# Power.net
KiCad netlist of a schematic drawn in Altium Designer
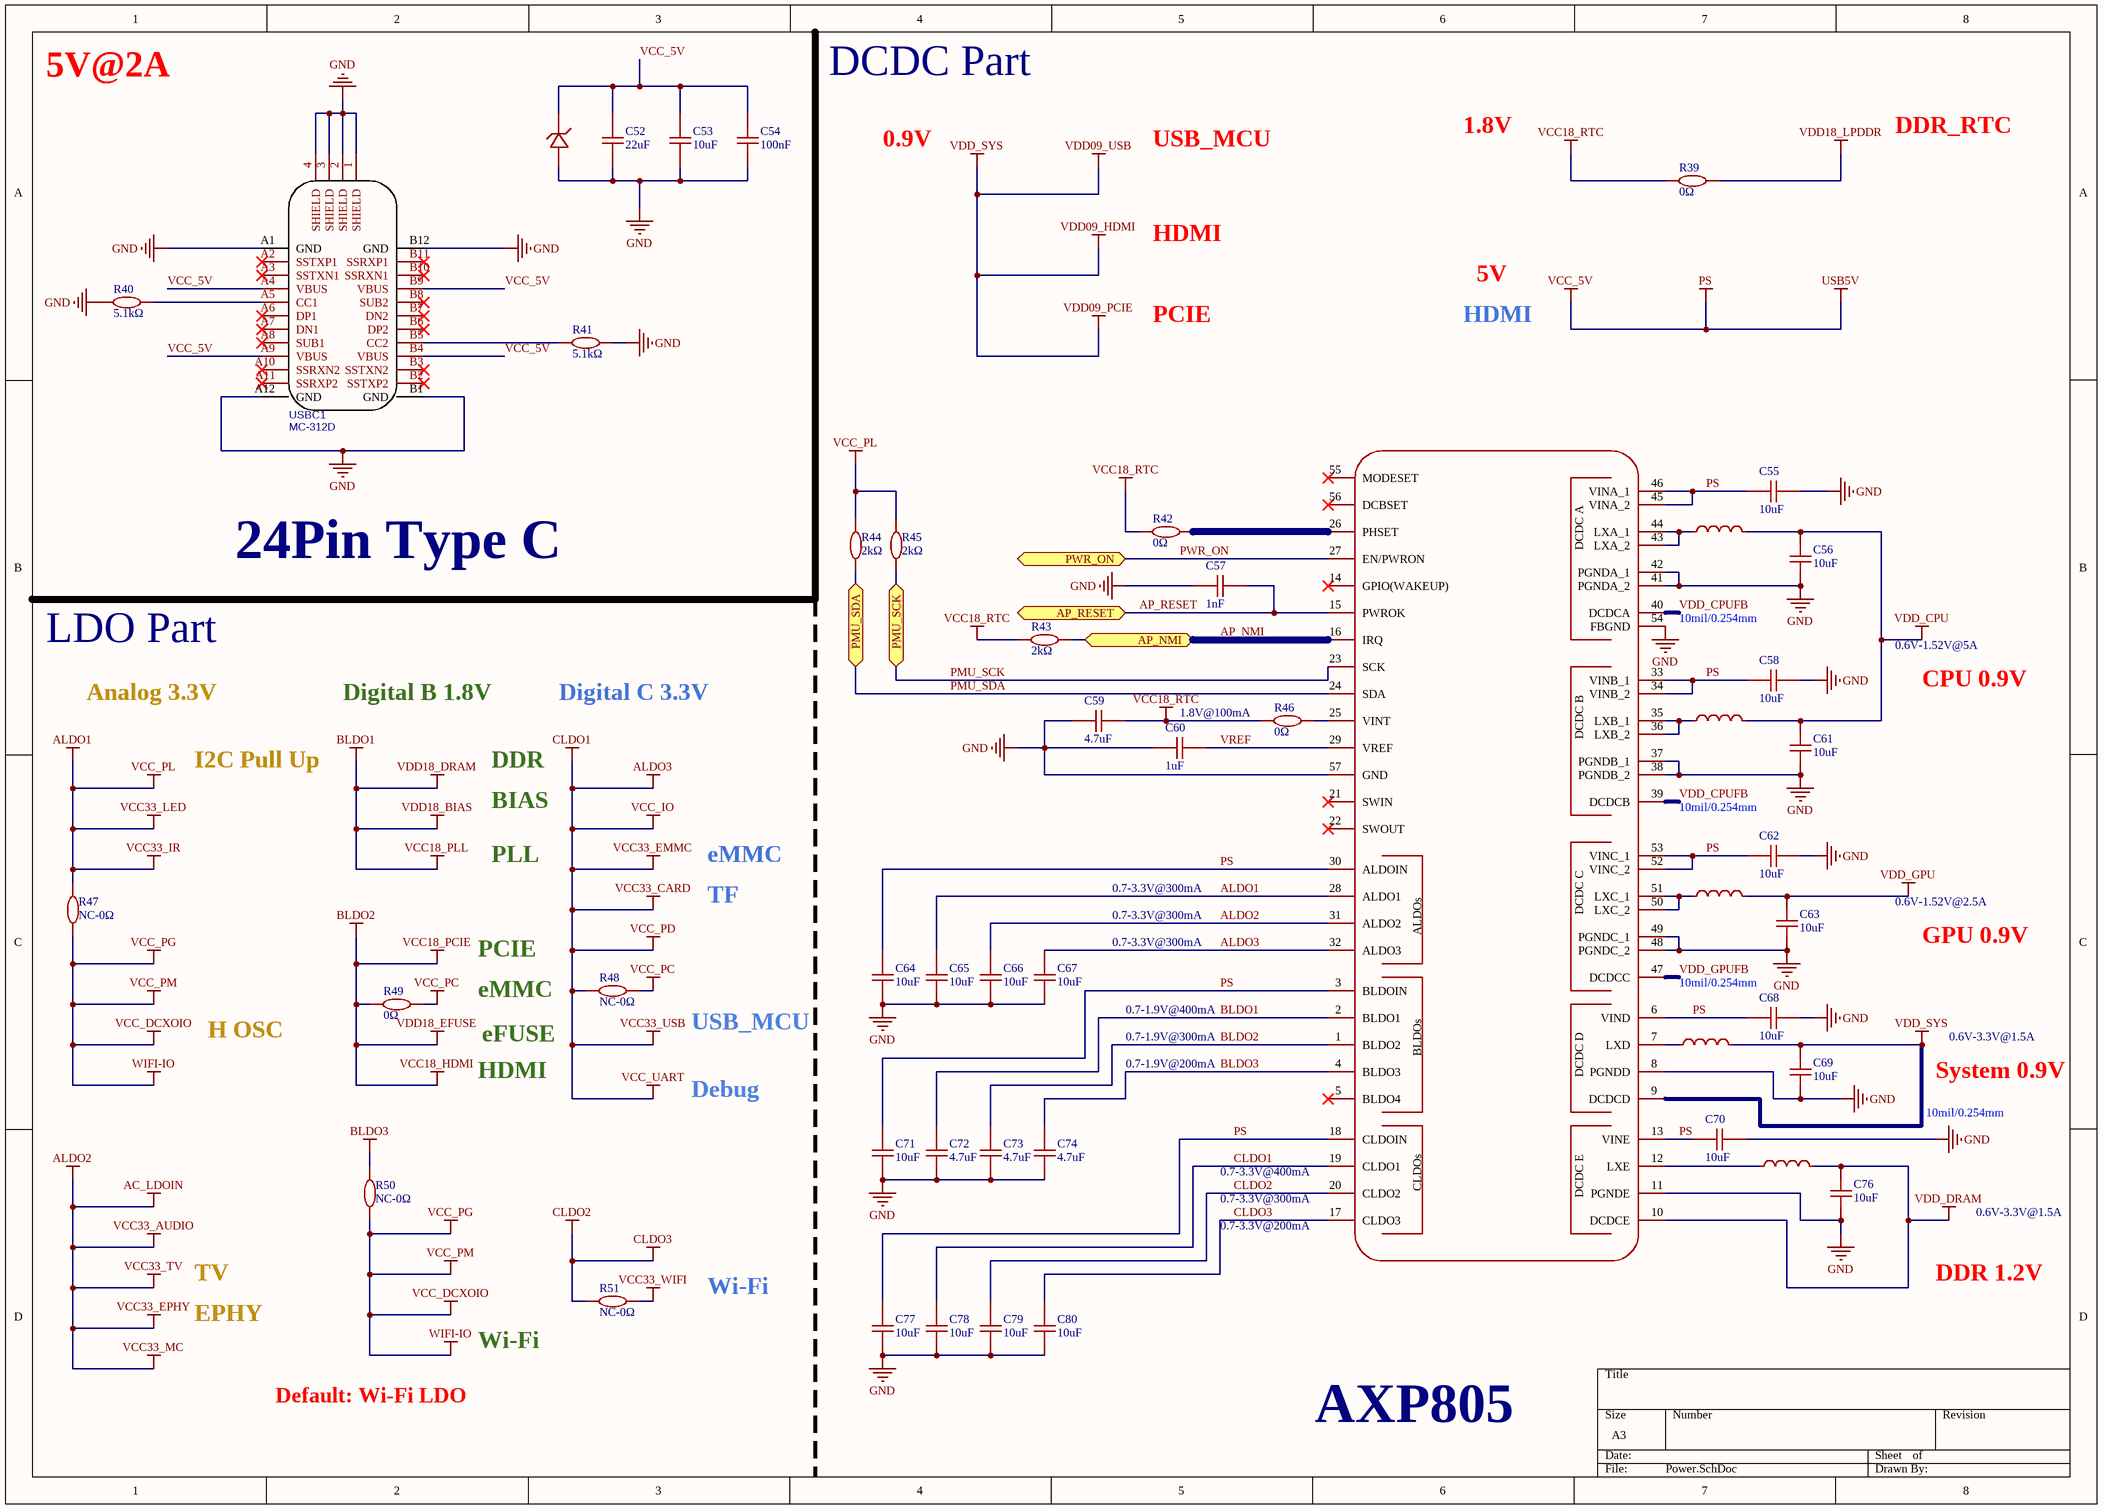
[diagram p0: Power.SchDoc]

(export (version "E")
  (design (tool "Eeschema 10.0.6"))
  (components
    (comp (ref "C52")
      (value "22uF")
      (footprint "C0603")
      (description "16V 22uF X5R ±20% 0603 Ceramic Capacitors ROHS")
      (libsource (lib "RLC") (part "22uF"))
    )
    (comp (ref "C53")
      (value "10uF")
      (footprint "C0603")
      (description "10V 10uF X5R ±10% 0603 Ceramic Capacitors ROHS")
      (libsource (lib "RLC") (part "10uF"))
    )
    (comp (ref "C54")
      (value "100nF")
      (footprint "C0402")
      (description "50V 100nF X7R ±10% 0402 Ceramic Capacitors ROHS")
      (libsource (lib "RLC") (part "100nF"))
    )
    (comp (ref "C55")
      (value "10uF")
      (footprint "C0603")
      (description "10V 10uF X5R ±10% 0603 Ceramic Capacitors ROHS")
      (libsource (lib "RLC") (part "10uF"))
    )
    (comp (ref "C56")
      (value "10uF")
      (footprint "C0603")
      (description "10V 10uF X5R ±10% 0603 Ceramic Capacitors ROHS")
      (libsource (lib "RLC") (part "10uF"))
    )
    (comp (ref "C57")
      (value "1nF")
      (footprint "C0402")
      (description "50V 1nF X7R ±10% 0402 Ceramic Capacitors ROHS")
      (libsource (lib "RLC") (part "1nF"))
    )
    (comp (ref "C58")
      (value "10uF")
      (footprint "C0603")
      (description "10V 10uF X5R ±10% 0603 Ceramic Capacitors ROHS")
      (libsource (lib "RLC") (part "10uF"))
    )
    (comp (ref "C59")
      (value "4.7uF")
      (footprint "C0402")
      (description "10V 4.7uF X5R ±20% 0402 Ceramic Capacitors ROHS")
      (libsource (lib "RLC") (part "4.7uF"))
    )
    (comp (ref "C60")
      (value "1uF")
      (footprint "C0402")
      (description "50V 1uF X5R ±10% 0402 Ceramic Capacitors ROHS")
      (libsource (lib "RLC") (part "1uF"))
    )
    (comp (ref "C61")
      (value "10uF")
      (footprint "C0603")
      (description "10V 10uF X5R ±10% 0603 Ceramic Capacitors ROHS")
      (libsource (lib "RLC") (part "10uF"))
    )
    (comp (ref "C62")
      (value "10uF")
      (footprint "C0603")
      (description "10V 10uF X5R ±10% 0603 Ceramic Capacitors ROHS")
      (libsource (lib "RLC") (part "10uF"))
    )
    (comp (ref "C63")
      (value "10uF")
      (footprint "C0603")
      (description "10V 10uF X5R ±10% 0603 Ceramic Capacitors ROHS")
      (libsource (lib "RLC") (part "10uF"))
    )
    (comp (ref "C64")
      (value "10uF")
      (footprint "C0603")
      (description "10V 10uF X5R ±10% 0603 Ceramic Capacitors ROHS")
      (libsource (lib "RLC") (part "10uF"))
    )
    (comp (ref "C65")
      (value "10uF")
      (footprint "C0603")
      (description "10V 10uF X5R ±10% 0603 Ceramic Capacitors ROHS")
      (libsource (lib "RLC") (part "10uF"))
    )
    (comp (ref "C66")
      (value "10uF")
      (footprint "C0603")
      (description "10V 10uF X5R ±10% 0603 Ceramic Capacitors ROHS")
      (libsource (lib "RLC") (part "10uF"))
    )
    (comp (ref "C67")
      (value "10uF")
      (footprint "C0603")
      (description "10V 10uF X5R ±10% 0603 Ceramic Capacitors ROHS")
      (libsource (lib "RLC") (part "10uF"))
    )
    (comp (ref "C68")
      (value "10uF")
      (footprint "C0603")
      (description "10V 10uF X5R ±10% 0603 Ceramic Capacitors ROHS")
      (libsource (lib "RLC") (part "10uF"))
    )
    (comp (ref "C69")
      (value "10uF")
      (footprint "C0603")
      (description "10V 10uF X5R ±10% 0603 Ceramic Capacitors ROHS")
      (libsource (lib "RLC") (part "10uF"))
    )
    (comp (ref "C70")
      (value "10uF")
      (footprint "C0603")
      (description "10V 10uF X5R ±10% 0603 Ceramic Capacitors ROHS")
      (libsource (lib "RLC") (part "10uF"))
    )
    (comp (ref "C71")
      (value "10uF")
      (footprint "C0603")
      (description "10V 10uF X5R ±10% 0603 Ceramic Capacitors ROHS")
      (libsource (lib "RLC") (part "10uF"))
    )
    (comp (ref "C72")
      (value "4.7uF")
      (footprint "C0402")
      (description "10V 4.7uF X5R ±20% 0402 Ceramic Capacitors ROHS")
      (libsource (lib "RLC") (part "4.7uF"))
    )
    (comp (ref "C73")
      (value "4.7uF")
      (footprint "C0402")
      (description "10V 4.7uF X5R ±20% 0402 Ceramic Capacitors ROHS")
      (libsource (lib "RLC") (part "4.7uF"))
    )
    (comp (ref "C74")
      (value "4.7uF")
      (footprint "C0402")
      (description "10V 4.7uF X5R ±20% 0402 Ceramic Capacitors ROHS")
      (libsource (lib "RLC") (part "4.7uF"))
    )
    (comp (ref "C76")
      (value "10uF")
      (footprint "C0603")
      (description "10V 10uF X5R ±10% 0603 Ceramic Capacitors ROHS")
      (libsource (lib "RLC") (part "10uF"))
    )
    (comp (ref "C77")
      (value "10uF")
      (footprint "C0603")
      (description "10V 10uF X5R ±10% 0603 Ceramic Capacitors ROHS")
      (libsource (lib "RLC") (part "10uF"))
    )
    (comp (ref "C78")
      (value "10uF")
      (footprint "C0603")
      (description "10V 10uF X5R ±10% 0603 Ceramic Capacitors ROHS")
      (libsource (lib "RLC") (part "10uF"))
    )
    (comp (ref "C79")
      (value "10uF")
      (footprint "C0603")
      (description "10V 10uF X5R ±10% 0603 Ceramic Capacitors ROHS")
      (libsource (lib "RLC") (part "10uF"))
    )
    (comp (ref "C80")
      (value "10uF")
      (footprint "C0603")
      (description "10V 10uF X5R ±10% 0603 Ceramic Capacitors ROHS")
      (libsource (lib "RLC") (part "10uF"))
    )
    (comp (ref "D5")
      (value "SMAJ5.0A")
      (footprint "SMA_L4.3-W2.6-LS5.2-RD")
      (description "43.5A 400W 9.2V 6.4V Unidirectional 5V DO-214AC(SMA) TVS Diodes ROHS")
      (fields (field (name "MANUFACTURER") "Littelfuse(美国力特)"))
      (libsource (lib "LED") (part "SMAJ5.0A_C83329"))
    )
    (comp (ref "L2")
      (value "1.5uH")
      (footprint "IND-SMD_L4.0-W4.0")
      (description "4.15A 1.5uH ±30% 18mΩ SMD,4x4mm Fixed Inductors ROHS")
      (fields
        (field (name "MANUFACTURER") "Sunltech(顺磁)")
        (field (name "MANUFACTURER PART") "SLW4030S1R0NST")
      )
      (libsource (lib "RLC") (part "SLW4030S1R5NST"))
    )
    (comp (ref "L3")
      (value "1.5uH")
      (footprint "IND-SMD_L4.0-W4.0")
      (description "4.15A 1.5uH ±30% 18mΩ SMD,4x4mm Fixed Inductors ROHS")
      (fields
        (field (name "MANUFACTURER") "Sunltech(顺磁)")
        (field (name "MANUFACTURER PART") "SLW4030S1R0NST")
      )
      (libsource (lib "RLC") (part "SLW4030S1R5NST"))
    )
    (comp (ref "L4")
      (value "1.5uH")
      (footprint "IND-SMD_L4.0-W4.0")
      (description "4.15A 1.5uH ±30% 18mΩ SMD,4x4mm Fixed Inductors ROHS")
      (fields
        (field (name "MANUFACTURER") "Sunltech(顺磁)")
        (field (name "MANUFACTURER PART") "SLW4030S1R0NST")
      )
      (libsource (lib "RLC") (part "SLW4030S1R5NST"))
    )
    (comp (ref "L5")
      (value "1.5uH")
      (footprint "IND-SMD_L4.0-W4.0")
      (description "4.15A 1.5uH ±30% 18mΩ SMD,4x4mm Fixed Inductors ROHS")
      (fields
        (field (name "MANUFACTURER") "Sunltech(顺磁)")
        (field (name "MANUFACTURER PART") "SLW4030S1R0NST")
      )
      (libsource (lib "RLC") (part "SLW4030S1R5NST"))
    )
    (comp (ref "L6")
      (value "1.5uH")
      (footprint "IND-SMD_L4.0-W4.0")
      (description "4.15A 1.5uH ±30% 18mΩ SMD,4x4mm Fixed Inductors ROHS")
      (fields
        (field (name "MANUFACTURER") "Sunltech(顺磁)")
        (field (name "MANUFACTURER PART") "SLW4030S1R0NST")
      )
      (libsource (lib "RLC") (part "SLW4030S1R5NST"))
    )
    (comp (ref "R39")
      (value "0Ω")
      (footprint "R0402")
      (description "0Ω 62.5mW 50V Thick Film Resistor ±1% 0402 Chip Resistor - Surface Mount ROHS")
      (libsource (lib "RLC") (part "0Ω"))
    )
    (comp (ref "R40")
      (value "5.1kΩ")
      (footprint "R0402")
      (description "5.1kΩ 62.5mW 50V ±100ppm/℃ Thick Film Resistor ±1% 0402 Chip Resistor - Surface Mount ROHS")
      (libsource (lib "RLC") (part "5.1kΩ"))
    )
    (comp (ref "R41")
      (value "5.1kΩ")
      (footprint "R0402")
      (description "5.1kΩ 62.5mW 50V ±100ppm/℃ Thick Film Resistor ±1% 0402 Chip Resistor - Surface Mount ROHS")
      (libsource (lib "RLC") (part "5.1kΩ"))
    )
    (comp (ref "R42")
      (value "0Ω")
      (footprint "R0402")
      (description "0Ω 62.5mW 50V Thick Film Resistor ±1% 0402 Chip Resistor - Surface Mount ROHS")
      (libsource (lib "RLC") (part "0Ω"))
    )
    (comp (ref "R43")
      (value "2kΩ")
      (footprint "R0402")
      (description "100mW 2kΩ 75V ±100ppm/℃ Thick Film Resistor ±1% 0402 Chip Resistor - Surface Mount ROHS")
      (libsource (lib "RLC") (part "2kΩ"))
    )
    (comp (ref "R44")
      (value "2kΩ")
      (footprint "R0402")
      (description "100mW 2kΩ 75V ±100ppm/℃ Thick Film Resistor ±1% 0402 Chip Resistor - Surface Mount ROHS")
      (libsource (lib "RLC") (part "2kΩ"))
    )
    (comp (ref "R45")
      (value "2kΩ")
      (footprint "R0402")
      (description "100mW 2kΩ 75V ±100ppm/℃ Thick Film Resistor ±1% 0402 Chip Resistor - Surface Mount ROHS")
      (libsource (lib "RLC") (part "2kΩ"))
    )
    (comp (ref "R46")
      (value "0Ω")
      (footprint "R0402")
      (description "0Ω 62.5mW 50V Thick Film Resistor ±1% 0402 Chip Resistor - Surface Mount ROHS")
      (libsource (lib "RLC") (part "0Ω"))
    )
    (comp (ref "R47")
      (value "NC-0Ω")
      (footprint "R0402")
      (description "0Ω 62.5mW 50V Thick Film Resistor ±1% 0402 Chip Resistor - Surface Mount ROHS")
      (libsource (lib "RLC") (part "0Ω"))
    )
    (comp (ref "R48")
      (value "NC-0Ω")
      (footprint "R0402")
      (description "0Ω 62.5mW 50V Thick Film Resistor ±1% 0402 Chip Resistor - Surface Mount ROHS")
      (libsource (lib "RLC") (part "0Ω"))
    )
    (comp (ref "R49")
      (value "0Ω")
      (footprint "R0402")
      (description "0Ω 62.5mW 50V Thick Film Resistor ±1% 0402 Chip Resistor - Surface Mount ROHS")
      (libsource (lib "RLC") (part "0Ω"))
    )
    (comp (ref "R50")
      (value "NC-0Ω")
      (footprint "R0402")
      (description "0Ω 62.5mW 50V Thick Film Resistor ±1% 0402 Chip Resistor - Surface Mount ROHS")
      (libsource (lib "RLC") (part "0Ω"))
    )
    (comp (ref "R51")
      (value "NC-0Ω")
      (footprint "R0402")
      (description "0Ω 62.5mW 50V Thick Film Resistor ±1% 0402 Chip Resistor - Surface Mount ROHS")
      (libsource (lib "RLC") (part "0Ω"))
    )
    (comp (ref "U4")
      (value "AXP805")
      (footprint "QFN-56_L7.0-W7.0-P0.40-TL-EP4.6")
      (libsource (lib "IC") (part "AXP805"))
    )
    (comp (ref "USBC1")
      (value "MC-312D")
      (footprint "USB-C-SMD_MC-312D-C")
      (description "1 24P Type-C SMD USB, DVI, HDMI Connector Assemblies ROHS")
      (fields
        (field (name "MANUFACTURER") "SOFNG(硕方)")
        (field (name "MANUFACTURER PART") "MC-312D-C")
        (field (name "CONTRIBUTOR") "LCSC")
      )
      (libsource (lib "Connector") (part "MC-312D"))
    )
  )
  (nets
    (net (code "1") (name "/AP_NMI") (class "Default")
      (node (ref "R43") (pin "2") (pinfunction "2_2") (pintype "passive"))
      (node (ref "U4") (pin "16") (pinfunction "IRQ_16") (pintype "passive"))
    )
    (net (code "2") (name "/AP_RESET") (class "Default")
      (node (ref "C57") (pin "2") (pinfunction "2_2") (pintype "passive"))
      (node (ref "U4") (pin "15") (pinfunction "PWROK_15") (pintype "passive"))
    )
    (net (code "3") (name "/PMU_SCK") (class "Default")
      (node (ref "R45") (pin "1") (pinfunction "1_1") (pintype "passive"))
      (node (ref "U4") (pin "23") (pinfunction "SCK_23") (pintype "passive"))
    )
    (net (code "4") (name "/PMU_SDA") (class "Default")
      (node (ref "R44") (pin "1") (pinfunction "1_1") (pintype "passive"))
      (node (ref "U4") (pin "24") (pinfunction "SDA_24") (pintype "passive"))
    )
    (net (code "5") (name "/PWR_ON") (class "Default")
      (node (ref "U4") (pin "27") (pinfunction "EN/PWRON_27") (pintype "passive"))
    )
    (net (code "6") (name "/VDD_CPUFB") (class "Default")
      (node (ref "U4") (pin "39") (pinfunction "DCDCB_39") (pintype "passive"))
      (node (ref "U4") (pin "40") (pinfunction "DCDCA_40") (pintype "passive"))
    )
    (net (code "7") (name "/VDD_GPUFB") (class "Default")
      (node (ref "U4") (pin "47") (pinfunction "DCDCC_47") (pintype "passive"))
    )
    (net (code "8") (name "/VREF") (class "Default")
      (node (ref "C60") (pin "2") (pinfunction "2_2") (pintype "passive"))
      (node (ref "U4") (pin "29") (pinfunction "VREF_29") (pintype "passive"))
    )
    (net (code "9") (name "AC_LDOIN") (class "Default")
      (node (ref "C66") (pin "2") (pinfunction "2_2") (pintype "passive"))
      (node (ref "U4") (pin "31") (pinfunction "ALDO2_31") (pintype "passive"))
    )
    (net (code "10") (name "ALDO1") (class "Default")
      (node (ref "C65") (pin "2") (pinfunction "2_2") (pintype "passive"))
      (node (ref "R44") (pin "2") (pinfunction "2_2") (pintype "passive"))
      (node (ref "R45") (pin "2") (pinfunction "2_2") (pintype "passive"))
      (node (ref "R47") (pin "2") (pinfunction "2_2") (pintype "passive"))
      (node (ref "U4") (pin "28") (pinfunction "ALDO1_28") (pintype "passive"))
    )
    (net (code "11") (name "ALDO3") (class "Default")
      (node (ref "C67") (pin "2") (pinfunction "2_2") (pintype "passive"))
      (node (ref "C78") (pin "2") (pinfunction "2_2") (pintype "passive"))
      (node (ref "R48") (pin "2") (pinfunction "2_2") (pintype "passive"))
      (node (ref "U4") (pin "19") (pinfunction "CLDO1_19") (pintype "passive"))
      (node (ref "U4") (pin "32") (pinfunction "ALDO3_32") (pintype "passive"))
    )
    (net (code "12") (name "BLDO1") (class "Default")
      (node (ref "C72") (pin "2") (pinfunction "2_2") (pintype "passive"))
      (node (ref "U4") (pin "2") (pinfunction "BLDO1_2") (pintype "passive"))
    )
    (net (code "13") (name "BLDO2") (class "Default")
      (node (ref "C73") (pin "2") (pinfunction "2_2") (pintype "passive"))
      (node (ref "R49") (pin "1") (pinfunction "1_1") (pintype "passive"))
      (node (ref "U4") (pin "1") (pinfunction "BLDO2_1") (pintype "passive"))
    )
    (net (code "14") (name "BLDO3") (class "Default")
      (node (ref "C74") (pin "2") (pinfunction "2_2") (pintype "passive"))
      (node (ref "R50") (pin "2") (pinfunction "2_2") (pintype "passive"))
      (node (ref "U4") (pin "4") (pinfunction "BLDO3_4") (pintype "passive"))
    )
    (net (code "15") (name "CLDO2") (class "Default")
      (node (ref "C79") (pin "2") (pinfunction "2_2") (pintype "passive"))
      (node (ref "C80") (pin "2") (pinfunction "2_2") (pintype "passive"))
      (node (ref "R51") (pin "2") (pinfunction "2_2") (pintype "passive"))
      (node (ref "U4") (pin "17") (pinfunction "CLDO3_17") (pintype "passive"))
      (node (ref "U4") (pin "20") (pinfunction "CLDO2_20") (pintype "passive"))
    )
    (net (code "16") (name "GND") (class "Default")
      (node (ref "C52") (pin "1") (pinfunction "1_1") (pintype "passive"))
      (node (ref "C53") (pin "1") (pinfunction "1_1") (pintype "passive"))
      (node (ref "C54") (pin "1") (pinfunction "1_1") (pintype "passive"))
      (node (ref "C55") (pin "1") (pinfunction "1_1") (pintype "passive"))
      (node (ref "C56") (pin "1") (pinfunction "1_1") (pintype "passive"))
      (node (ref "C57") (pin "1") (pinfunction "1_1") (pintype "passive"))
      (node (ref "C58") (pin "1") (pinfunction "1_1") (pintype "passive"))
      (node (ref "C59") (pin "1") (pinfunction "1_1") (pintype "passive"))
      (node (ref "C60") (pin "1") (pinfunction "1_1") (pintype "passive"))
      (node (ref "C61") (pin "1") (pinfunction "1_1") (pintype "passive"))
      (node (ref "C62") (pin "1") (pinfunction "1_1") (pintype "passive"))
      (node (ref "C63") (pin "1") (pinfunction "1_1") (pintype "passive"))
      (node (ref "C64") (pin "1") (pinfunction "1_1") (pintype "passive"))
      (node (ref "C65") (pin "1") (pinfunction "1_1") (pintype "passive"))
      (node (ref "C66") (pin "1") (pinfunction "1_1") (pintype "passive"))
      (node (ref "C67") (pin "1") (pinfunction "1_1") (pintype "passive"))
      (node (ref "C68") (pin "1") (pinfunction "1_1") (pintype "passive"))
      (node (ref "C69") (pin "1") (pinfunction "1_1") (pintype "passive"))
      (node (ref "C70") (pin "1") (pinfunction "1_1") (pintype "passive"))
      (node (ref "C71") (pin "1") (pinfunction "1_1") (pintype "passive"))
      (node (ref "C72") (pin "1") (pinfunction "1_1") (pintype "passive"))
      (node (ref "C73") (pin "1") (pinfunction "1_1") (pintype "passive"))
      (node (ref "C74") (pin "1") (pinfunction "1_1") (pintype "passive"))
      (node (ref "C76") (pin "1") (pinfunction "1_1") (pintype "passive"))
      (node (ref "C77") (pin "1") (pinfunction "1_1") (pintype "passive"))
      (node (ref "C78") (pin "1") (pinfunction "1_1") (pintype "passive"))
      (node (ref "C79") (pin "1") (pinfunction "1_1") (pintype "passive"))
      (node (ref "C80") (pin "1") (pinfunction "1_1") (pintype "passive"))
      (node (ref "D5") (pin "2") (pinfunction "A_2") (pintype "passive"))
      (node (ref "R40") (pin "1") (pinfunction "1_1") (pintype "passive"))
      (node (ref "R41") (pin "2") (pinfunction "2_2") (pintype "passive"))
      (node (ref "U4") (pin "11") (pinfunction "PGNDE_11") (pintype "passive"))
      (node (ref "U4") (pin "37") (pinfunction "PGNDB_1_37") (pintype "passive"))
      (node (ref "U4") (pin "38") (pinfunction "PGNDB_2_38") (pintype "passive"))
      (node (ref "U4") (pin "41") (pinfunction "PGNDA_2_41") (pintype "passive"))
      (node (ref "U4") (pin "42") (pinfunction "PGNDA_1_42") (pintype "passive"))
      (node (ref "U4") (pin "48") (pinfunction "PGNDC_2_48") (pintype "passive"))
      (node (ref "U4") (pin "49") (pinfunction "PGNDC_1_49") (pintype "passive"))
      (node (ref "U4") (pin "54") (pinfunction "FBGND_54") (pintype "passive"))
      (node (ref "U4") (pin "57") (pinfunction "GND_57") (pintype "passive"))
      (node (ref "U4") (pin "8") (pinfunction "PGNDD_8") (pintype "passive"))
      (node (ref "USBC1") (pin "1") (pinfunction "SHIELD_1") (pintype "passive"))
      (node (ref "USBC1") (pin "2") (pinfunction "SHIELD_2") (pintype "passive"))
      (node (ref "USBC1") (pin "3") (pinfunction "SHIELD_3") (pintype "passive"))
      (node (ref "USBC1") (pin "4") (pinfunction "SHIELD_4") (pintype "passive"))
      (node (ref "USBC1") (pin "A1") (pinfunction "GND_A1") (pintype "passive"))
      (node (ref "USBC1") (pin "A12") (pinfunction "GND_A12") (pintype "passive"))
      (node (ref "USBC1") (pin "B1") (pinfunction "GND_B1") (pintype "passive"))
      (node (ref "USBC1") (pin "B12") (pinfunction "GND_B12") (pintype "passive"))
    )
    (net (code "17") (name "Net-(U4-LXA_1)") (class "Default")
      (node (ref "L2") (pin "1") (pinfunction "1_1") (pintype "passive"))
      (node (ref "U4") (pin "43") (pinfunction "LXA_2_43") (pintype "passive"))
      (node (ref "U4") (pin "44") (pinfunction "LXA_1_44") (pintype "passive"))
    )
    (net (code "18") (name "Net-(U4-LXB_1)") (class "Default")
      (node (ref "L3") (pin "1") (pinfunction "1_1") (pintype "passive"))
      (node (ref "U4") (pin "35") (pinfunction "LXB_1_35") (pintype "passive"))
      (node (ref "U4") (pin "36") (pinfunction "LXB_2_36") (pintype "passive"))
    )
    (net (code "19") (name "Net-(U4-LXC_1)") (class "Default")
      (node (ref "L4") (pin "1") (pinfunction "1_1") (pintype "passive"))
      (node (ref "U4") (pin "50") (pinfunction "LXC_2_50") (pintype "passive"))
      (node (ref "U4") (pin "51") (pinfunction "LXC_1_51") (pintype "passive"))
    )
    (net (code "20") (name "Net-(U4-LXD)") (class "Default")
      (node (ref "L5") (pin "1") (pinfunction "1_1") (pintype "passive"))
      (node (ref "U4") (pin "7") (pinfunction "LXD_7") (pintype "passive"))
    )
    (net (code "21") (name "Net-(U4-LXE)") (class "Default")
      (node (ref "L6") (pin "1") (pinfunction "1_1") (pintype "passive"))
      (node (ref "U4") (pin "12") (pinfunction "LXE_12") (pintype "passive"))
    )
    (net (code "22") (name "Net-(U4-PHSET)") (class "Default")
      (node (ref "R42") (pin "2") (pinfunction "2_2") (pintype "passive"))
      (node (ref "U4") (pin "26") (pinfunction "PHSET_26") (pintype "passive"))
    )
    (net (code "23") (name "Net-(U4-VINT)") (class "Default")
      (node (ref "R46") (pin "2") (pinfunction "2_2") (pintype "passive"))
      (node (ref "U4") (pin "25") (pinfunction "VINT_25") (pintype "passive"))
    )
    (net (code "24") (name "Net-(USBC1-CC1)") (class "Default")
      (node (ref "R40") (pin "2") (pinfunction "2_2") (pintype "passive"))
      (node (ref "USBC1") (pin "A5") (pinfunction "CC1_A5") (pintype "passive"))
    )
    (net (code "25") (name "Net-(USBC1-CC2)") (class "Default")
      (node (ref "R41") (pin "1") (pinfunction "1_1") (pintype "passive"))
      (node (ref "USBC1") (pin "B5") (pinfunction "CC2_B5") (pintype "passive"))
    )
    (net (code "26") (name "PS") (class "Default")
      (node (ref "C52") (pin "2") (pinfunction "2_2") (pintype "passive"))
      (node (ref "C53") (pin "2") (pinfunction "2_2") (pintype "passive"))
      (node (ref "C54") (pin "2") (pinfunction "2_2") (pintype "passive"))
      (node (ref "C55") (pin "2") (pinfunction "2_2") (pintype "passive"))
      (node (ref "C58") (pin "2") (pinfunction "2_2") (pintype "passive"))
      (node (ref "C62") (pin "2") (pinfunction "2_2") (pintype "passive"))
      (node (ref "C64") (pin "2") (pinfunction "2_2") (pintype "passive"))
      (node (ref "C68") (pin "2") (pinfunction "2_2") (pintype "passive"))
      (node (ref "C70") (pin "2") (pinfunction "2_2") (pintype "passive"))
      (node (ref "C71") (pin "2") (pinfunction "2_2") (pintype "passive"))
      (node (ref "C77") (pin "2") (pinfunction "2_2") (pintype "passive"))
      (node (ref "D5") (pin "1") (pinfunction "C_1") (pintype "passive"))
      (node (ref "U4") (pin "13") (pinfunction "VINE_13") (pintype "passive"))
      (node (ref "U4") (pin "18") (pinfunction "CLDOIN_18") (pintype "passive"))
      (node (ref "U4") (pin "3") (pinfunction "BLDOIN_3") (pintype "passive"))
      (node (ref "U4") (pin "30") (pinfunction "ALDOIN_30") (pintype "passive"))
      (node (ref "U4") (pin "33") (pinfunction "VINB_1_33") (pintype "passive"))
      (node (ref "U4") (pin "34") (pinfunction "VINB_2_34") (pintype "passive"))
      (node (ref "U4") (pin "45") (pinfunction "VINA_2_45") (pintype "passive"))
      (node (ref "U4") (pin "46") (pinfunction "VINA_1_46") (pintype "passive"))
      (node (ref "U4") (pin "52") (pinfunction "VINC_2_52") (pintype "passive"))
      (node (ref "U4") (pin "53") (pinfunction "VINC_1_53") (pintype "passive"))
      (node (ref "U4") (pin "6") (pinfunction "VIND_6") (pintype "passive"))
      (node (ref "USBC1") (pin "A4") (pinfunction "VBUS_A4") (pintype "passive"))
      (node (ref "USBC1") (pin "A9") (pinfunction "VBUS_A9") (pintype "passive"))
      (node (ref "USBC1") (pin "B4") (pinfunction "VBUS_B4") (pintype "passive"))
      (node (ref "USBC1") (pin "B9") (pinfunction "VBUS_B9") (pintype "passive"))
    )
    (net (code "27") (name "VCC18_RTC") (class "Default")
      (node (ref "C59") (pin "2") (pinfunction "2_2") (pintype "passive"))
      (node (ref "R39") (pin "1") (pinfunction "1_1") (pintype "passive"))
      (node (ref "R42") (pin "1") (pinfunction "1_1") (pintype "passive"))
      (node (ref "R43") (pin "1") (pinfunction "1_1") (pintype "passive"))
      (node (ref "R46") (pin "1") (pinfunction "1_1") (pintype "passive"))
    )
    (net (code "28") (name "VCC33_WIFI") (class "Default")
      (node (ref "R51") (pin "1") (pinfunction "1_1") (pintype "passive"))
    )
    (net (code "29") (name "VCC_DCXOIO") (class "Default")
      (node (ref "R47") (pin "1") (pinfunction "1_1") (pintype "passive"))
      (node (ref "R50") (pin "1") (pinfunction "1_1") (pintype "passive"))
    )
    (net (code "30") (name "VCC_PC") (class "Default")
      (node (ref "R48") (pin "1") (pinfunction "1_1") (pintype "passive"))
      (node (ref "R49") (pin "2") (pinfunction "2_2") (pintype "passive"))
    )
    (net (code "31") (name "VDD09_HDMI") (class "Default")
      (node (ref "C69") (pin "2") (pinfunction "2_2") (pintype "passive"))
      (node (ref "L5") (pin "2") (pinfunction "2_2") (pintype "passive"))
      (node (ref "U4") (pin "9") (pinfunction "DCDCD_9") (pintype "passive"))
    )
    (net (code "32") (name "VDD18_LPDDR") (class "Default")
      (node (ref "R39") (pin "2") (pinfunction "2_2") (pintype "passive"))
    )
    (net (code "33") (name "VDD_CPU") (class "Default")
      (node (ref "C56") (pin "2") (pinfunction "2_2") (pintype "passive"))
      (node (ref "C61") (pin "2") (pinfunction "2_2") (pintype "passive"))
      (node (ref "L2") (pin "2") (pinfunction "2_2") (pintype "passive"))
      (node (ref "L3") (pin "2") (pinfunction "2_2") (pintype "passive"))
    )
    (net (code "34") (name "VDD_DRAM") (class "Default")
      (node (ref "C76") (pin "2") (pinfunction "2_2") (pintype "passive"))
      (node (ref "L6") (pin "2") (pinfunction "2_2") (pintype "passive"))
      (node (ref "U4") (pin "10") (pinfunction "DCDCE_10") (pintype "passive"))
    )
    (net (code "35") (name "VDD_GPU") (class "Default")
      (node (ref "C63") (pin "2") (pinfunction "2_2") (pintype "passive"))
      (node (ref "L4") (pin "2") (pinfunction "2_2") (pintype "passive"))
    )
    (net (code "36") (name "unconnected-(U4-BLDO4-Pad5)") (class "Default")
      (node (ref "U4") (pin "5") (pinfunction "BLDO4_5") (pintype "passive+no_connect"))
    )
    (net (code "37") (name "unconnected-(U4-DCBSET-Pad56)") (class "Default")
      (node (ref "U4") (pin "56") (pinfunction "DCBSET_56") (pintype "passive+no_connect"))
    )
    (net (code "38") (name "unconnected-(U4-GPIO(WAKEUP)-Pad14)") (class "Default")
      (node (ref "U4") (pin "14") (pinfunction "GPIO(WAKEUP)_14") (pintype "passive+no_connect"))
    )
    (net (code "39") (name "unconnected-(U4-MODESET-Pad55)") (class "Default")
      (node (ref "U4") (pin "55") (pinfunction "MODESET_55") (pintype "passive+no_connect"))
    )
    (net (code "40") (name "unconnected-(U4-SWIN-Pad21)") (class "Default")
      (node (ref "U4") (pin "21") (pinfunction "SWIN_21") (pintype "passive+no_connect"))
    )
    (net (code "41") (name "unconnected-(U4-SWOUT-Pad22)") (class "Default")
      (node (ref "U4") (pin "22") (pinfunction "SWOUT_22") (pintype "passive+no_connect"))
    )
    (net (code "42") (name "unconnected-(USBC1-DN1-PadA7)") (class "Default")
      (node (ref "USBC1") (pin "A7") (pinfunction "DN1_A7") (pintype "passive+no_connect"))
    )
    (net (code "43") (name "unconnected-(USBC1-DN2-PadB7)") (class "Default")
      (node (ref "USBC1") (pin "B7") (pinfunction "DN2_B7") (pintype "passive+no_connect"))
    )
    (net (code "44") (name "unconnected-(USBC1-DP1-PadA6)") (class "Default")
      (node (ref "USBC1") (pin "A6") (pinfunction "DP1_A6") (pintype "passive+no_connect"))
    )
    (net (code "45") (name "unconnected-(USBC1-DP2-PadB6)") (class "Default")
      (node (ref "USBC1") (pin "B6") (pinfunction "DP2_B6") (pintype "passive+no_connect"))
    )
    (net (code "46") (name "unconnected-(USBC1-SSRXN1-PadB10)") (class "Default")
      (node (ref "USBC1") (pin "B10") (pinfunction "SSRXN1_B10") (pintype "passive+no_connect"))
    )
    (net (code "47") (name "unconnected-(USBC1-SSRXN2-PadA10)") (class "Default")
      (node (ref "USBC1") (pin "A10") (pinfunction "SSRXN2_A10") (pintype "passive+no_connect"))
    )
    (net (code "48") (name "unconnected-(USBC1-SSRXP1-PadB11)") (class "Default")
      (node (ref "USBC1") (pin "B11") (pinfunction "SSRXP1_B11") (pintype "passive+no_connect"))
    )
    (net (code "49") (name "unconnected-(USBC1-SSRXP2-PadA11)") (class "Default")
      (node (ref "USBC1") (pin "A11") (pinfunction "SSRXP2_A11") (pintype "passive+no_connect"))
    )
    (net (code "50") (name "unconnected-(USBC1-SSTXN1-PadA3)") (class "Default")
      (node (ref "USBC1") (pin "A3") (pinfunction "SSTXN1_A3") (pintype "passive+no_connect"))
    )
    (net (code "51") (name "unconnected-(USBC1-SSTXN2-PadB3)") (class "Default")
      (node (ref "USBC1") (pin "B3") (pinfunction "SSTXN2_B3") (pintype "passive+no_connect"))
    )
    (net (code "52") (name "unconnected-(USBC1-SSTXP1-PadA2)") (class "Default")
      (node (ref "USBC1") (pin "A2") (pinfunction "SSTXP1_A2") (pintype "passive+no_connect"))
    )
    (net (code "53") (name "unconnected-(USBC1-SSTXP2-PadB2)") (class "Default")
      (node (ref "USBC1") (pin "B2") (pinfunction "SSTXP2_B2") (pintype "passive+no_connect"))
    )
    (net (code "54") (name "unconnected-(USBC1-SUB1-PadA8)") (class "Default")
      (node (ref "USBC1") (pin "A8") (pinfunction "SUB1_A8") (pintype "passive+no_connect"))
    )
    (net (code "55") (name "unconnected-(USBC1-SUB2-PadB8)") (class "Default")
      (node (ref "USBC1") (pin "B8") (pinfunction "SUB2_B8") (pintype "passive+no_connect"))
    )
  )
)
